# Welder_PSU_02.net
KiCad netlist of a schematic drawn in EAGLE
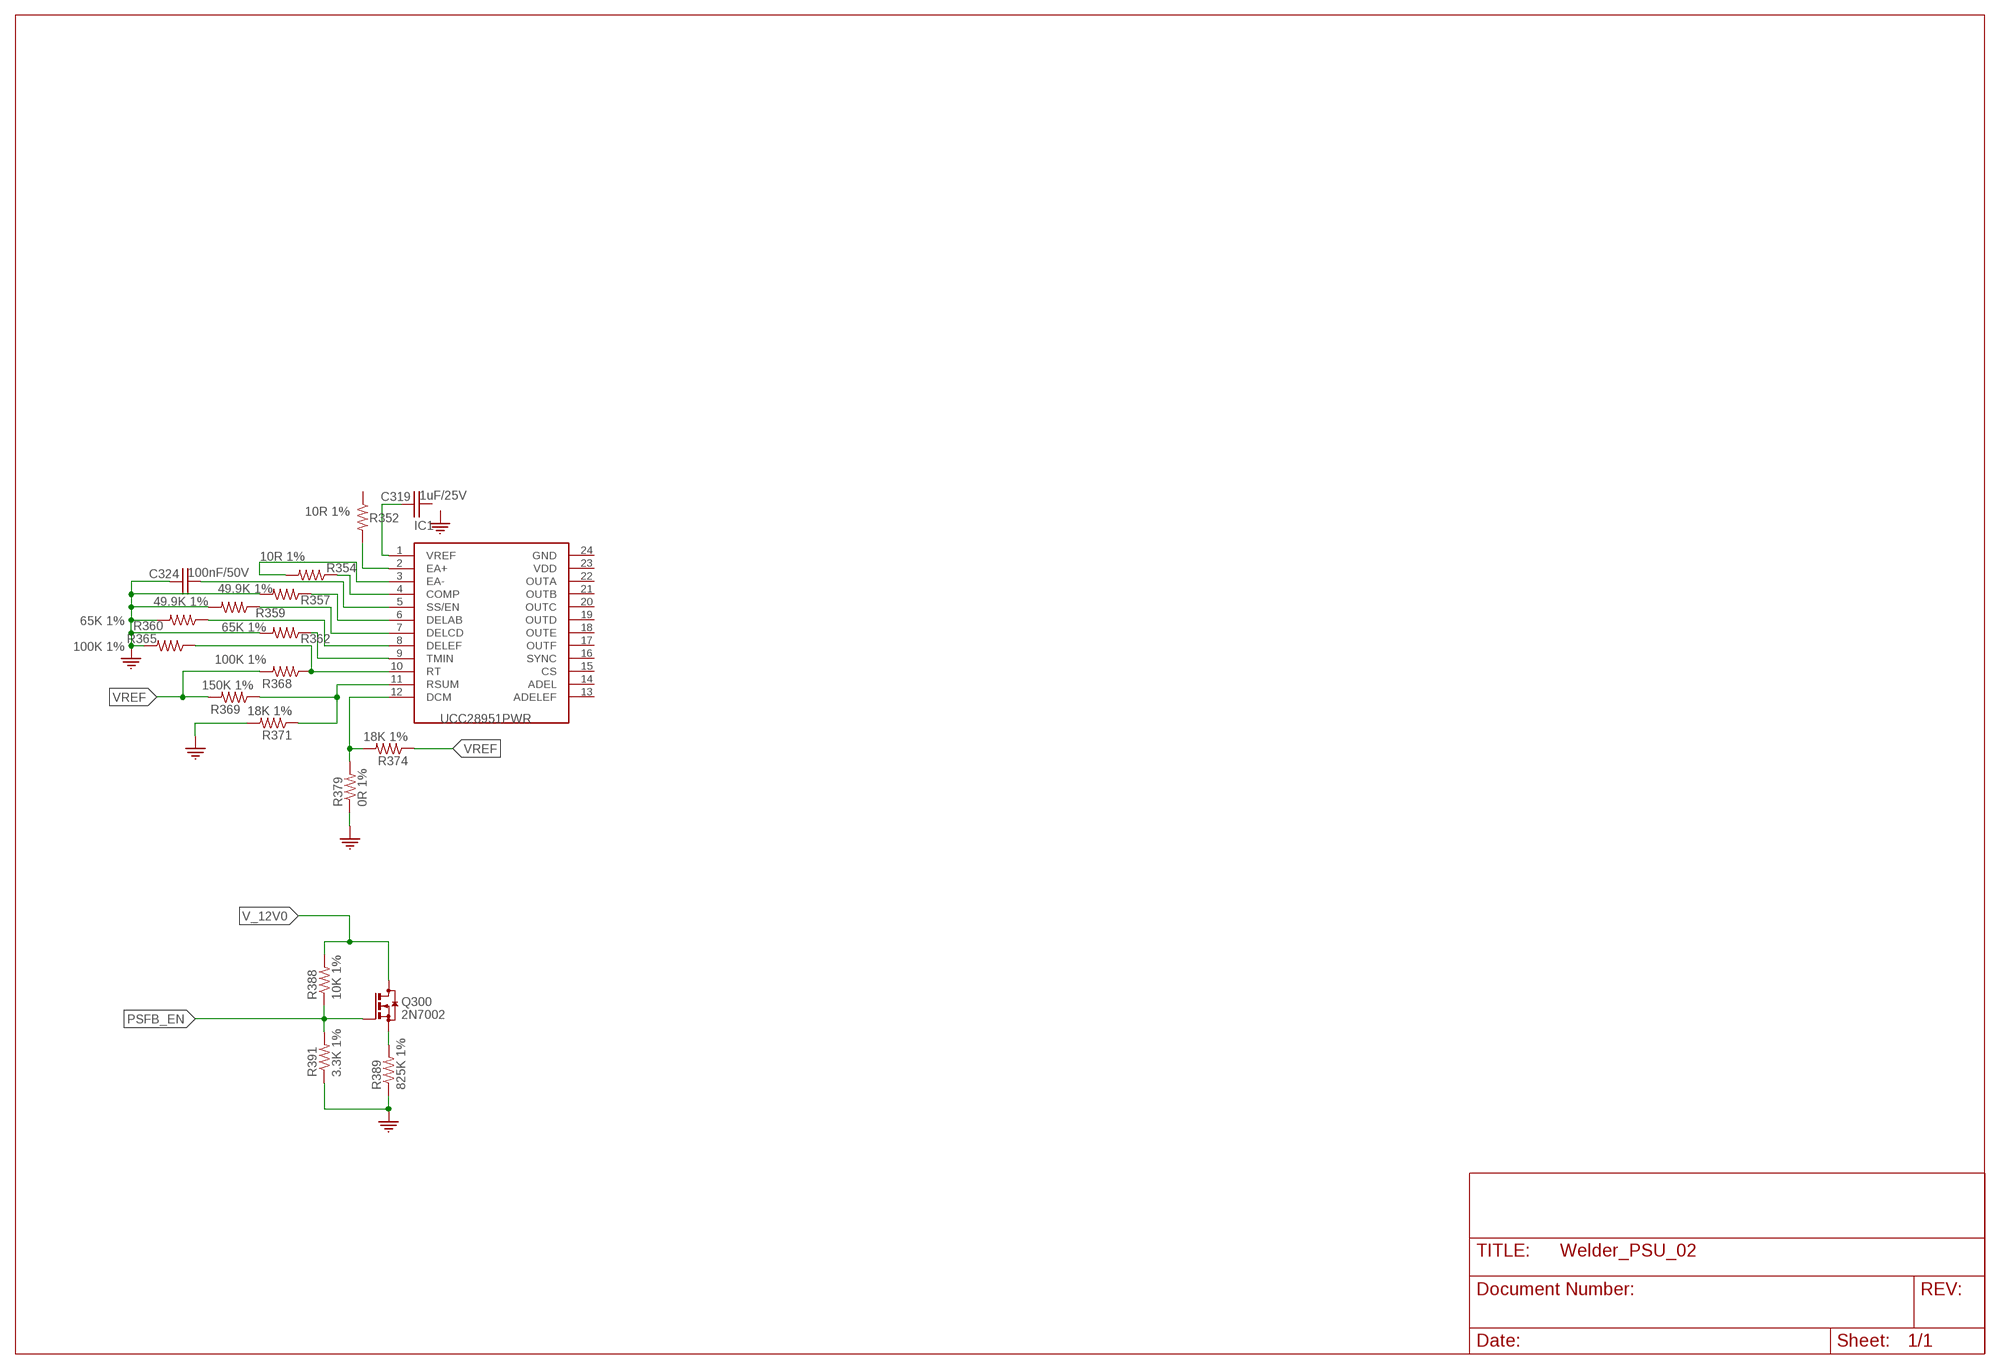
[diagram p0: schematic, sheet 1]

(export (version "E")
  (design (tool "Eeschema 10.0.6"))
  (components
    (comp (ref "C319")
      (value "1uF/25V")
      (footprint "eagle-import:EIA0603")
      (libsource (lib "eagle-import") (part "C_0603EIA0603"))
    )
    (comp (ref "C324")
      (value "100nF/50V")
      (footprint "eagle-import:EIA0603")
      (libsource (lib "eagle-import") (part "C_0603EIA0603"))
    )
    (comp (ref "IC1")
      (value "UCC28951PWR")
      (footprint "eagle-import:TSSOP24")
      (fields (field (name "MFR") "Texas Instruments"))
      (libsource (lib "eagle-import") (part "UCC28951PWR"))
    )
    (comp (ref "Q300")
      (value "2N7002")
      (footprint "eagle-import:SOT23")
      (fields (field (name "MFR") "Diodes, Guangdong Hotetech,NXP"))
      (libsource (lib "eagle-import") (part "2N7002"))
    )
    (comp (ref "R352")
      (value "10R 1%")
      (footprint "eagle-import:EIA0603")
      (libsource (lib "eagle-import") (part "R_0603"))
    )
    (comp (ref "R354")
      (value "10R 1%")
      (footprint "eagle-import:EIA0603")
      (libsource (lib "eagle-import") (part "R_0603"))
    )
    (comp (ref "R357")
      (value "49.9K 1%")
      (footprint "eagle-import:EIA0603")
      (libsource (lib "eagle-import") (part "R_0603"))
    )
    (comp (ref "R359")
      (value "49.9K 1%")
      (footprint "eagle-import:EIA0603")
      (libsource (lib "eagle-import") (part "R_0603"))
    )
    (comp (ref "R360")
      (value "65K 1%")
      (footprint "eagle-import:EIA0603")
      (libsource (lib "eagle-import") (part "R_0603"))
    )
    (comp (ref "R362")
      (value "65K 1%")
      (footprint "eagle-import:EIA0603")
      (libsource (lib "eagle-import") (part "R_0603"))
    )
    (comp (ref "R365")
      (value "100K 1%")
      (footprint "eagle-import:EIA0603")
      (libsource (lib "eagle-import") (part "R_0603"))
    )
    (comp (ref "R368")
      (value "100K 1%")
      (footprint "eagle-import:EIA0603")
      (libsource (lib "eagle-import") (part "R_0603"))
    )
    (comp (ref "R369")
      (value "150K 1%")
      (footprint "eagle-import:EIA0603")
      (libsource (lib "eagle-import") (part "R_0603"))
    )
    (comp (ref "R371")
      (value "18K 1%")
      (footprint "eagle-import:EIA0603")
      (libsource (lib "eagle-import") (part "R_0603"))
    )
    (comp (ref "R374")
      (value "18K 1%")
      (footprint "eagle-import:EIA0603")
      (libsource (lib "eagle-import") (part "R_0603"))
    )
    (comp (ref "R379")
      (value "0R 1%")
      (footprint "eagle-import:EIA0603")
      (libsource (lib "eagle-import") (part "R_0603"))
    )
    (comp (ref "R388")
      (value "10K 1%")
      (footprint "eagle-import:EIA0603")
      (libsource (lib "eagle-import") (part "R_0603"))
    )
    (comp (ref "R389")
      (value "825K 1%")
      (footprint "eagle-import:EIA0603")
      (libsource (lib "eagle-import") (part "R_0603"))
    )
    (comp (ref "R391")
      (value "3.3K 1%")
      (footprint "eagle-import:EIA0603")
      (libsource (lib "eagle-import") (part "R_0603"))
    )
  )
  (nets
    (net (code "1") (name "GND") (class "Default")
      (node (ref "C324") (pin "1") (pinfunction "1_1") (pintype "passive"))
      (node (ref "R357") (pin "2") (pinfunction "2_2") (pintype "passive"))
      (node (ref "R359") (pin "2") (pinfunction "2_2") (pintype "passive"))
      (node (ref "R360") (pin "2") (pinfunction "2_2") (pintype "passive"))
      (node (ref "R362") (pin "2") (pinfunction "2_2") (pintype "passive"))
      (node (ref "R365") (pin "2") (pinfunction "2_2") (pintype "passive"))
      (node (ref "R371") (pin "2") (pinfunction "2_2") (pintype "passive"))
      (node (ref "R379") (pin "1") (pinfunction "1_1") (pintype "passive"))
      (node (ref "R389") (pin "1") (pinfunction "1_1") (pintype "passive"))
      (node (ref "R391") (pin "1") (pinfunction "1_1") (pintype "passive"))
    )
    (net (code "2") (name "Net-(IC1-COMP)") (class "Default")
      (node (ref "IC1") (pin "4") (pinfunction "COMP_4") (pintype "bidirectional"))
      (node (ref "R354") (pin "1") (pinfunction "1_1") (pintype "passive"))
    )
    (net (code "3") (name "Net-(IC1-DCM)") (class "Default")
      (node (ref "IC1") (pin "12") (pinfunction "DCM_12") (pintype "bidirectional"))
      (node (ref "R374") (pin "2") (pinfunction "2_2") (pintype "passive"))
      (node (ref "R379") (pin "2") (pinfunction "2_2") (pintype "passive"))
    )
    (net (code "4") (name "Net-(IC1-DELAB)") (class "Default")
      (node (ref "IC1") (pin "6") (pinfunction "DELAB_6") (pintype "bidirectional"))
      (node (ref "R357") (pin "1") (pinfunction "1_1") (pintype "passive"))
    )
    (net (code "5") (name "Net-(IC1-DELCD)") (class "Default")
      (node (ref "IC1") (pin "7") (pinfunction "DELCD_7") (pintype "bidirectional"))
      (node (ref "R359") (pin "1") (pinfunction "1_1") (pintype "passive"))
    )
    (net (code "6") (name "Net-(IC1-DELEF)") (class "Default")
      (node (ref "IC1") (pin "8") (pinfunction "DELEF_8") (pintype "bidirectional"))
      (node (ref "R360") (pin "1") (pinfunction "1_1") (pintype "passive"))
    )
    (net (code "7") (name "Net-(IC1-EA+)") (class "Default")
      (node (ref "IC1") (pin "2") (pinfunction "EA+_2") (pintype "bidirectional"))
      (node (ref "R352") (pin "2") (pinfunction "2_2") (pintype "passive"))
    )
    (net (code "8") (name "Net-(IC1-EA-)") (class "Default")
      (node (ref "IC1") (pin "3") (pinfunction "EA-_3") (pintype "bidirectional"))
      (node (ref "R354") (pin "2") (pinfunction "2_2") (pintype "passive"))
    )
    (net (code "9") (name "Net-(IC1-RSUM)") (class "Default")
      (node (ref "IC1") (pin "11") (pinfunction "RSUM_11") (pintype "bidirectional"))
      (node (ref "R369") (pin "1") (pinfunction "1_1") (pintype "passive"))
      (node (ref "R371") (pin "1") (pinfunction "1_1") (pintype "passive"))
    )
    (net (code "10") (name "Net-(IC1-RT)") (class "Default")
      (node (ref "IC1") (pin "10") (pinfunction "RT_10") (pintype "bidirectional"))
      (node (ref "R365") (pin "1") (pinfunction "1_1") (pintype "passive"))
      (node (ref "R368") (pin "1") (pinfunction "1_1") (pintype "passive"))
    )
    (net (code "11") (name "Net-(IC1-SS{slash}EN)") (class "Default")
      (node (ref "C324") (pin "2") (pinfunction "2_2") (pintype "passive"))
      (node (ref "IC1") (pin "5") (pinfunction "SS/EN_5") (pintype "bidirectional"))
    )
    (net (code "12") (name "Net-(IC1-TMIN)") (class "Default")
      (node (ref "IC1") (pin "9") (pinfunction "TMIN_9") (pintype "bidirectional"))
      (node (ref "R362") (pin "1") (pinfunction "1_1") (pintype "passive"))
    )
    (net (code "13") (name "Net-(IC1-VREF)") (class "Default")
      (node (ref "C319") (pin "1") (pinfunction "1_1") (pintype "passive"))
      (node (ref "IC1") (pin "1") (pinfunction "VREF_1") (pintype "bidirectional"))
    )
    (net (code "14") (name "Net-(Q300-S)") (class "Default")
      (node (ref "Q300") (pin "2") (pinfunction "S_2") (pintype "passive"))
      (node (ref "R389") (pin "2") (pinfunction "2_2") (pintype "passive"))
    )
    (net (code "15") (name "PSFB_EN") (class "Default")
      (node (ref "Q300") (pin "1") (pinfunction "G_1") (pintype "passive"))
      (node (ref "R388") (pin "1") (pinfunction "1_1") (pintype "passive"))
      (node (ref "R391") (pin "2") (pinfunction "2_2") (pintype "passive"))
    )
    (net (code "16") (name "VREF") (class "Default")
      (node (ref "R368") (pin "2") (pinfunction "2_2") (pintype "passive"))
      (node (ref "R369") (pin "2") (pinfunction "2_2") (pintype "passive"))
      (node (ref "R374") (pin "1") (pinfunction "1_1") (pintype "passive"))
    )
    (net (code "17") (name "V_12V0") (class "Default")
      (node (ref "Q300") (pin "3") (pinfunction "D_3") (pintype "passive"))
      (node (ref "R388") (pin "2") (pinfunction "2_2") (pintype "passive"))
    )
    (net (code "18") (name "unconnected-(C319-Pad2)") (class "Default")
      (node (ref "C319") (pin "2") (pinfunction "2_2") (pintype "passive"))
    )
    (net (code "19") (name "unconnected-(IC1-ADEL-Pad14)") (class "Default")
      (node (ref "IC1") (pin "14") (pinfunction "ADEL_14") (pintype "bidirectional"))
    )
    (net (code "20") (name "unconnected-(IC1-ADELEF-Pad13)") (class "Default")
      (node (ref "IC1") (pin "13") (pinfunction "ADELEF_13") (pintype "bidirectional"))
    )
    (net (code "21") (name "unconnected-(IC1-CS-Pad15)") (class "Default")
      (node (ref "IC1") (pin "15") (pinfunction "CS_15") (pintype "bidirectional"))
    )
    (net (code "22") (name "unconnected-(IC1-GND-Pad24)") (class "Default")
      (node (ref "IC1") (pin "24") (pinfunction "GND_24") (pintype "bidirectional"))
    )
    (net (code "23") (name "unconnected-(IC1-OUTA-Pad22)") (class "Default")
      (node (ref "IC1") (pin "22") (pinfunction "OUTA_22") (pintype "bidirectional"))
    )
    (net (code "24") (name "unconnected-(IC1-OUTB-Pad21)") (class "Default")
      (node (ref "IC1") (pin "21") (pinfunction "OUTB_21") (pintype "bidirectional"))
    )
    (net (code "25") (name "unconnected-(IC1-OUTC-Pad20)") (class "Default")
      (node (ref "IC1") (pin "20") (pinfunction "OUTC_20") (pintype "bidirectional"))
    )
    (net (code "26") (name "unconnected-(IC1-OUTD-Pad19)") (class "Default")
      (node (ref "IC1") (pin "19") (pinfunction "OUTD_19") (pintype "bidirectional"))
    )
    (net (code "27") (name "unconnected-(IC1-OUTE-Pad18)") (class "Default")
      (node (ref "IC1") (pin "18") (pinfunction "OUTE_18") (pintype "bidirectional"))
    )
    (net (code "28") (name "unconnected-(IC1-OUTF-Pad17)") (class "Default")
      (node (ref "IC1") (pin "17") (pinfunction "OUTF_17") (pintype "bidirectional"))
    )
    (net (code "29") (name "unconnected-(IC1-SYNC-Pad16)") (class "Default")
      (node (ref "IC1") (pin "16") (pinfunction "SYNC_16") (pintype "bidirectional"))
    )
    (net (code "30") (name "unconnected-(IC1-VDD-Pad23)") (class "Default")
      (node (ref "IC1") (pin "23") (pinfunction "VDD_23") (pintype "bidirectional"))
    )
    (net (code "31") (name "unconnected-(R352-Pad1)") (class "Default")
      (node (ref "R352") (pin "1") (pinfunction "1_1") (pintype "passive"))
    )
  )
)
